# Powermeter.net
KiCad netlist of a schematic drawn in EAGLE
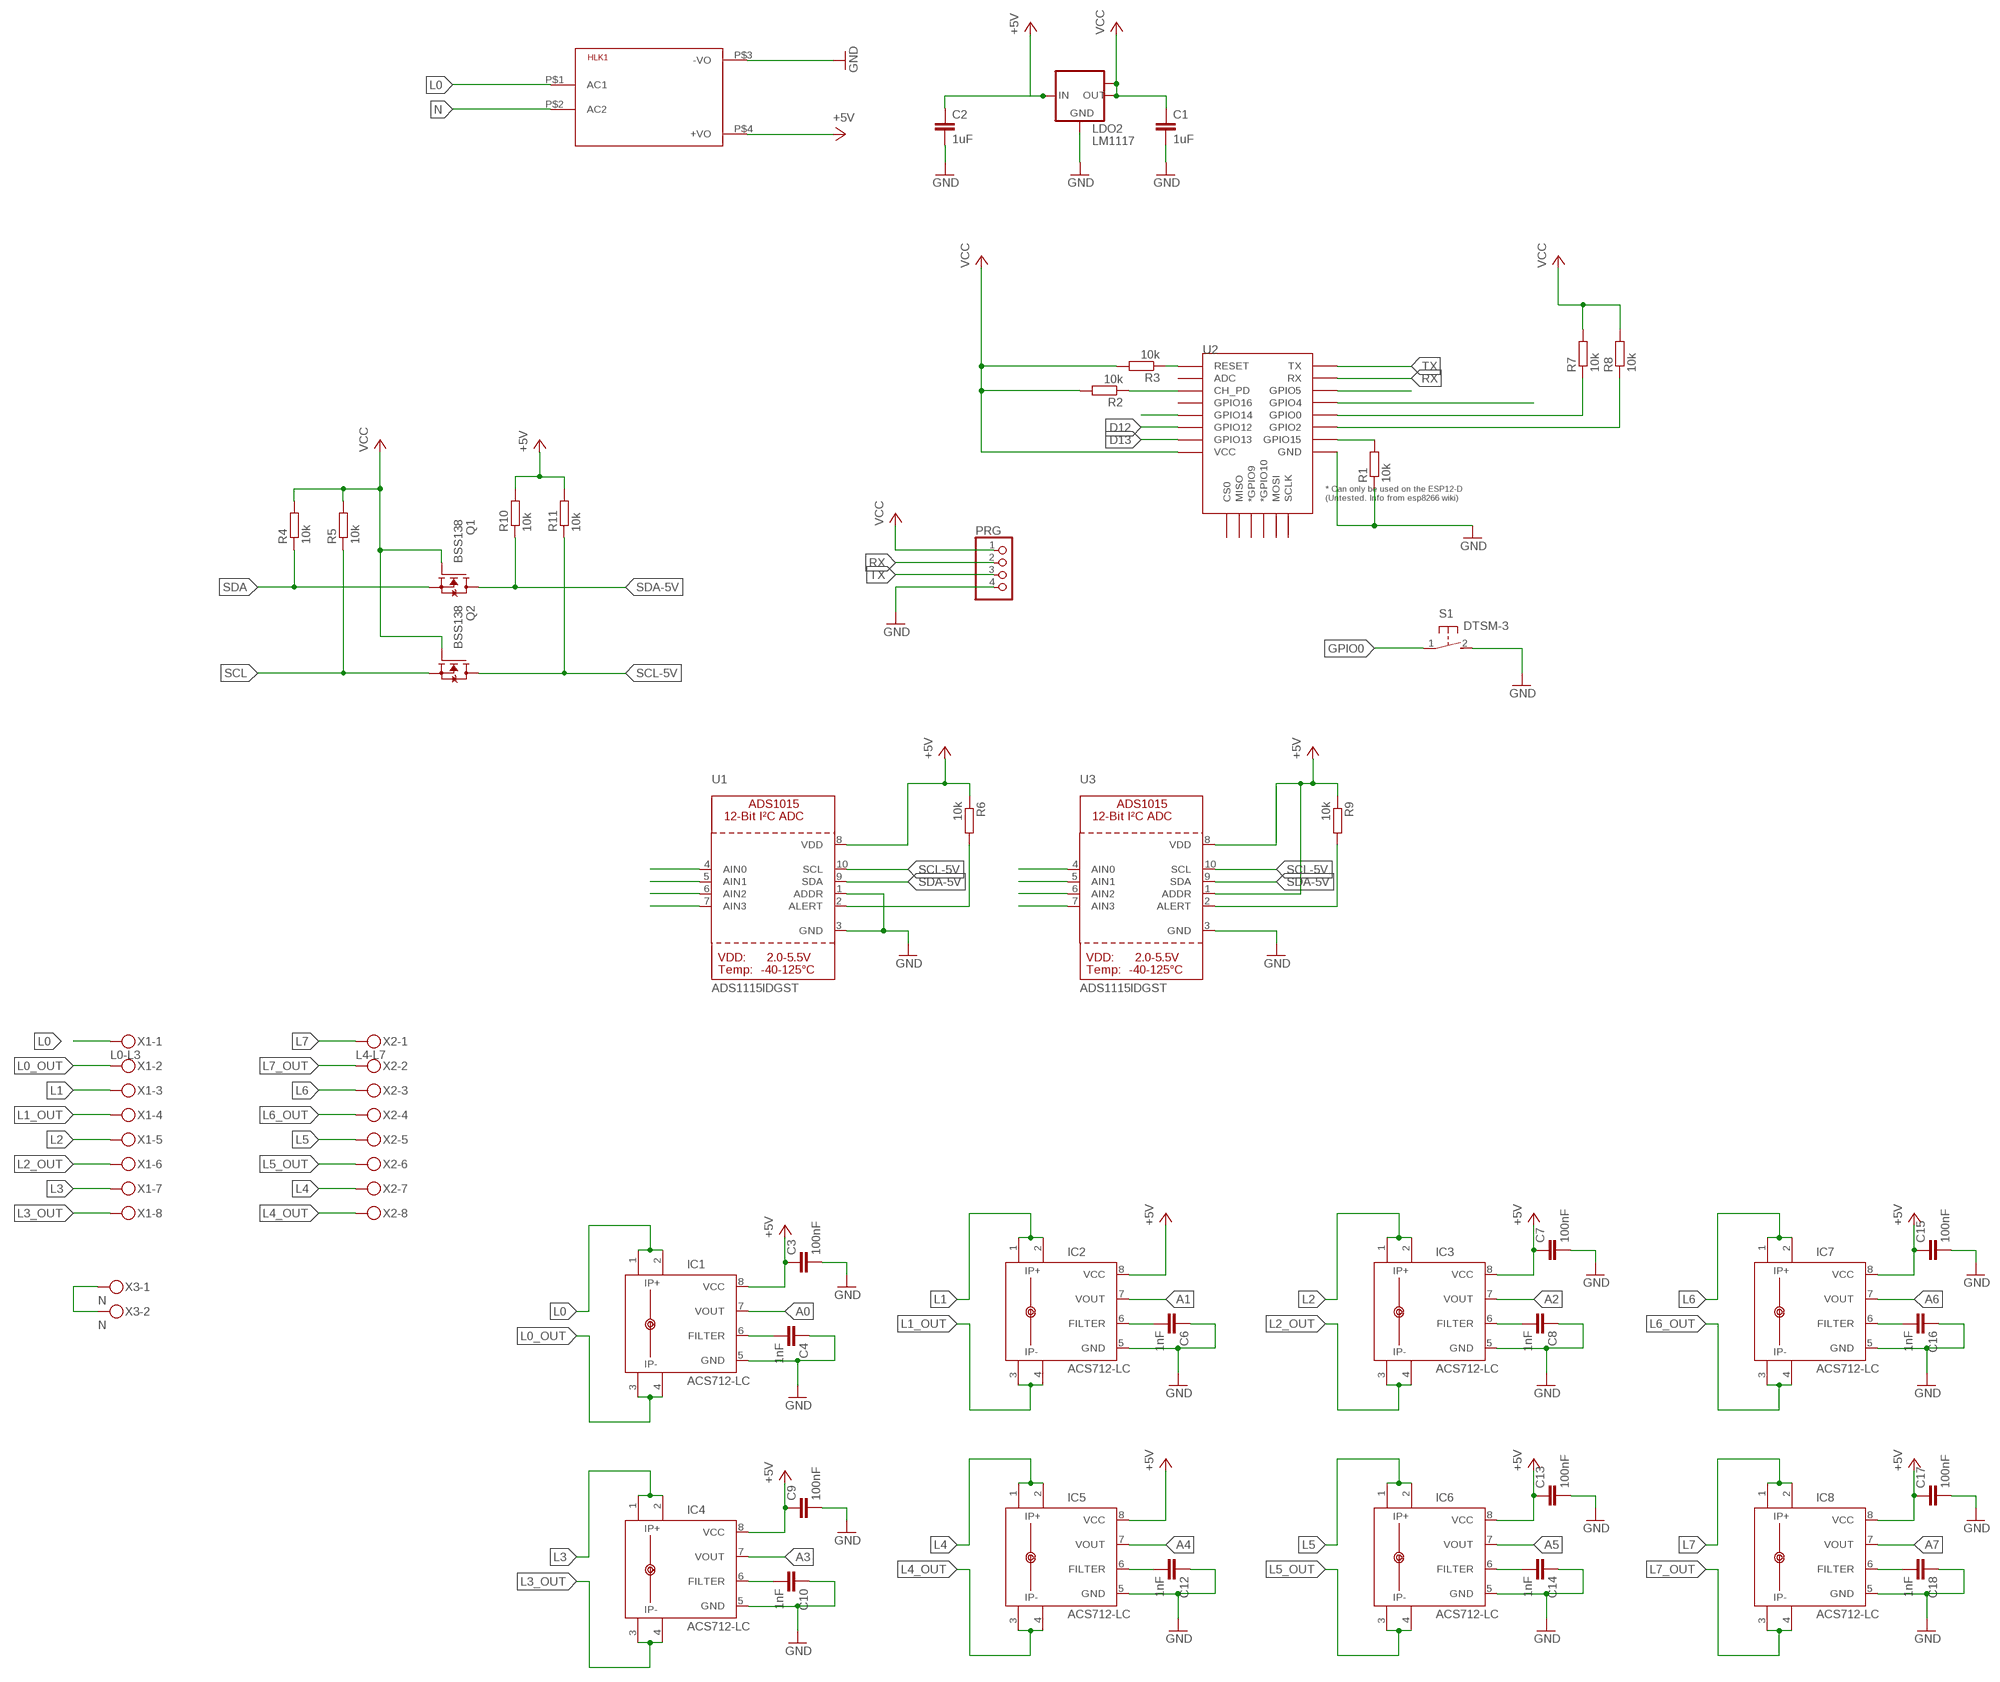
[diagram p0: schematic, sheet 1]

(export (version "E")
  (design (tool "Eeschema 10.0.6"))
  (components
    (comp (ref "C1")
      (value "1uF")
      (footprint "eagle-import:C0805")
      (libsource (lib "eagle-import") (part "C-EUC0805"))
    )
    (comp (ref "C2")
      (value "1uF")
      (footprint "eagle-import:C0805")
      (libsource (lib "eagle-import") (part "C-EUC0805"))
    )
    (comp (ref "C3")
      (value "100nF")
      (footprint "eagle-import:C0805")
      (libsource (lib "eagle-import") (part "C-EUC0805"))
    )
    (comp (ref "C4")
      (value "1nF")
      (footprint "eagle-import:C0805")
      (libsource (lib "eagle-import") (part "C-EUC0805"))
    )
    (comp (ref "C6")
      (value "1nF")
      (footprint "eagle-import:C0805")
      (libsource (lib "eagle-import") (part "C-EUC0805"))
    )
    (comp (ref "C7")
      (value "100nF")
      (footprint "eagle-import:C0805")
      (libsource (lib "eagle-import") (part "C-EUC0805"))
    )
    (comp (ref "C8")
      (value "1nF")
      (footprint "eagle-import:C0805")
      (libsource (lib "eagle-import") (part "C-EUC0805"))
    )
    (comp (ref "C9")
      (value "100nF")
      (footprint "eagle-import:C0805")
      (libsource (lib "eagle-import") (part "C-EUC0805"))
    )
    (comp (ref "C10")
      (value "1nF")
      (footprint "eagle-import:C0805")
      (libsource (lib "eagle-import") (part "C-EUC0805"))
    )
    (comp (ref "C12")
      (value "1nF")
      (footprint "eagle-import:C0805")
      (libsource (lib "eagle-import") (part "C-EUC0805"))
    )
    (comp (ref "C13")
      (value "100nF")
      (footprint "eagle-import:C0805")
      (libsource (lib "eagle-import") (part "C-EUC0805"))
    )
    (comp (ref "C14")
      (value "1nF")
      (footprint "eagle-import:C0805")
      (libsource (lib "eagle-import") (part "C-EUC0805"))
    )
    (comp (ref "C15")
      (value "100nF")
      (footprint "eagle-import:C0805")
      (libsource (lib "eagle-import") (part "C-EUC0805"))
    )
    (comp (ref "C16")
      (value "1nF")
      (footprint "eagle-import:C0805")
      (libsource (lib "eagle-import") (part "C-EUC0805"))
    )
    (comp (ref "C17")
      (value "100nF")
      (footprint "eagle-import:C0805")
      (libsource (lib "eagle-import") (part "C-EUC0805"))
    )
    (comp (ref "C18")
      (value "1nF")
      (footprint "eagle-import:C0805")
      (libsource (lib "eagle-import") (part "C-EUC0805"))
    )
    (comp (ref "HLK1")
      (value "HLK-PM013W")
      (footprint "eagle-import:HLK-PM01")
      (libsource (lib "eagle-import") (part "HLK-PM013W"))
    )
    (comp (ref "IC1")
      (value "ACS712-LC")
      (footprint "eagle-import:SOIC8")
      (libsource (lib "eagle-import") (part "ACS712-LC"))
    )
    (comp (ref "IC2")
      (value "ACS712-LC")
      (footprint "eagle-import:SOIC8")
      (libsource (lib "eagle-import") (part "ACS712-LC"))
    )
    (comp (ref "IC3")
      (value "ACS712-LC")
      (footprint "eagle-import:SOIC8")
      (libsource (lib "eagle-import") (part "ACS712-LC"))
    )
    (comp (ref "IC4")
      (value "ACS712-LC")
      (footprint "eagle-import:SOIC8")
      (libsource (lib "eagle-import") (part "ACS712-LC"))
    )
    (comp (ref "IC5")
      (value "ACS712-LC")
      (footprint "eagle-import:SOIC8")
      (libsource (lib "eagle-import") (part "ACS712-LC"))
    )
    (comp (ref "IC6")
      (value "ACS712-LC")
      (footprint "eagle-import:SOIC8")
      (libsource (lib "eagle-import") (part "ACS712-LC"))
    )
    (comp (ref "IC7")
      (value "ACS712-LC")
      (footprint "eagle-import:SOIC8")
      (libsource (lib "eagle-import") (part "ACS712-LC"))
    )
    (comp (ref "IC8")
      (value "ACS712-LC")
      (footprint "eagle-import:SOIC8")
      (libsource (lib "eagle-import") (part "ACS712-LC"))
    )
    (comp (ref "LDO2")
      (value "LM1117")
      (footprint "eagle-import:SOT223")
      (libsource (lib "eagle-import") (part "LM1117MPX-3.3"))
    )
    (comp (ref "PRG")
      (value "PINHD-1X04_2.54-S")
      (footprint "eagle-import:1X04-S")
      (libsource (lib "eagle-import") (part "PINHD-1X04_2.54-S"))
    )
    (comp (ref "Q1")
      (value "BSS138")
      (footprint "eagle-import:SOT23")
      (fields (field (name "MF") "Fairchild"))
      (libsource (lib "eagle-import") (part "BSS138"))
    )
    (comp (ref "Q2")
      (value "BSS138")
      (footprint "eagle-import:SOT23")
      (fields (field (name "MF") "Fairchild"))
      (libsource (lib "eagle-import") (part "BSS138"))
    )
    (comp (ref "R1")
      (value "10k")
      (footprint "eagle-import:R0805")
      (libsource (lib "eagle-import") (part "R-EU_R0805"))
    )
    (comp (ref "R2")
      (value "10k")
      (footprint "eagle-import:R0805")
      (libsource (lib "eagle-import") (part "R-EU_R0805"))
    )
    (comp (ref "R3")
      (value "10k")
      (footprint "eagle-import:R0805")
      (libsource (lib "eagle-import") (part "R-EU_R0805"))
    )
    (comp (ref "R4")
      (value "10k")
      (footprint "eagle-import:R0805")
      (libsource (lib "eagle-import") (part "R-EU_R0805"))
    )
    (comp (ref "R5")
      (value "10k")
      (footprint "eagle-import:R0805")
      (libsource (lib "eagle-import") (part "R-EU_R0805"))
    )
    (comp (ref "R6")
      (value "10k")
      (footprint "eagle-import:R0805")
      (libsource (lib "eagle-import") (part "R-EU_R0805"))
    )
    (comp (ref "R7")
      (value "10k")
      (footprint "eagle-import:R0805")
      (libsource (lib "eagle-import") (part "R-EU_R0805"))
    )
    (comp (ref "R8")
      (value "10k")
      (footprint "eagle-import:R0805")
      (libsource (lib "eagle-import") (part "R-EU_R0805"))
    )
    (comp (ref "R9")
      (value "10k")
      (footprint "eagle-import:R0805")
      (libsource (lib "eagle-import") (part "R-EU_R0805"))
    )
    (comp (ref "R10")
      (value "10k")
      (footprint "eagle-import:R0805")
      (libsource (lib "eagle-import") (part "R-EU_R0805"))
    )
    (comp (ref "R11")
      (value "10k")
      (footprint "eagle-import:R0805")
      (libsource (lib "eagle-import") (part "R-EU_R0805"))
    )
    (comp (ref "S1")
      (value "DTSM-3")
      (footprint "eagle-import:DTSM-3")
      (libsource (lib "eagle-import") (part "DTSM-3"))
    )
    (comp (ref "U1")
      (value "ADS1115IDGST")
      (footprint "eagle-import:MSOP10")
      (libsource (lib "eagle-import") (part "ADC_ADS1015"))
    )
    (comp (ref "U2")
      (value "ESP12ESMD")
      (footprint "eagle-import:ESP12E-SMD")
      (libsource (lib "eagle-import") (part "ESP12ESMD"))
    )
    (comp (ref "U3")
      (value "ADS1115IDGST")
      (footprint "eagle-import:MSOP10")
      (libsource (lib "eagle-import") (part "ADC_ADS1015"))
    )
    (comp (ref "X1")
      (value "L0-L3")
      (footprint "eagle-import:MKDSN1,5_8-5,08")
      (libsource (lib "eagle-import") (part "MKDSN1,5/8-5,08"))
    )
    (comp (ref "X2")
      (value "L4-L7")
      (footprint "eagle-import:MKDSN1,5_8-5,08")
      (libsource (lib "eagle-import") (part "MKDSN1,5/8-5,08"))
    )
    (comp (ref "X3")
      (value "N")
      (footprint "eagle-import:MKDSN1,5_2-5,08")
      (libsource (lib "eagle-import") (part "MKDSN1,5/2-5,08"))
    )
  )
  (nets
    (net (code "1") (name "+5V") (class "Default")
      (node (ref "C13") (pin "1") (pinfunction "1_1") (pintype "passive"))
      (node (ref "C15") (pin "1") (pinfunction "1_1") (pintype "passive"))
      (node (ref "C17") (pin "1") (pinfunction "1_1") (pintype "passive"))
      (node (ref "C2") (pin "1") (pinfunction "1_1") (pintype "passive"))
      (node (ref "C3") (pin "1") (pinfunction "1_1") (pintype "passive"))
      (node (ref "C7") (pin "1") (pinfunction "1_1") (pintype "passive"))
      (node (ref "C9") (pin "1") (pinfunction "1_1") (pintype "passive"))
      (node (ref "HLK1") (pin "P$4") (pinfunction "+VO_P$4") (pintype "bidirectional"))
      (node (ref "IC1") (pin "8") (pinfunction "VCC_8") (pintype "power_in"))
      (node (ref "IC2") (pin "8") (pinfunction "VCC_8") (pintype "power_in"))
      (node (ref "IC3") (pin "8") (pinfunction "VCC_8") (pintype "power_in"))
      (node (ref "IC4") (pin "8") (pinfunction "VCC_8") (pintype "power_in"))
      (node (ref "IC5") (pin "8") (pinfunction "VCC_8") (pintype "power_in"))
      (node (ref "IC6") (pin "8") (pinfunction "VCC_8") (pintype "power_in"))
      (node (ref "IC7") (pin "8") (pinfunction "VCC_8") (pintype "power_in"))
      (node (ref "IC8") (pin "8") (pinfunction "VCC_8") (pintype "power_in"))
      (node (ref "LDO2") (pin "3") (pinfunction "IN_3") (pintype "input"))
      (node (ref "R10") (pin "2") (pinfunction "2_2") (pintype "passive"))
      (node (ref "R11") (pin "2") (pinfunction "2_2") (pintype "passive"))
      (node (ref "R6") (pin "1") (pinfunction "1_1") (pintype "passive"))
      (node (ref "R9") (pin "1") (pinfunction "1_1") (pintype "passive"))
      (node (ref "U1") (pin "8") (pinfunction "VDD_8") (pintype "bidirectional"))
      (node (ref "U3") (pin "1") (pinfunction "ADDR_1") (pintype "bidirectional"))
      (node (ref "U3") (pin "8") (pinfunction "VDD_8") (pintype "bidirectional"))
    )
    (net (code "2") (name "A0") (class "Default")
      (node (ref "IC1") (pin "7") (pinfunction "VOUT_7") (pintype "output"))
      (node (ref "U1") (pin "4") (pinfunction "AIN0_4") (pintype "bidirectional"))
    )
    (net (code "3") (name "A1") (class "Default")
      (node (ref "IC2") (pin "7") (pinfunction "VOUT_7") (pintype "output"))
      (node (ref "U1") (pin "5") (pinfunction "AIN1_5") (pintype "bidirectional"))
    )
    (net (code "4") (name "A2") (class "Default")
      (node (ref "IC3") (pin "7") (pinfunction "VOUT_7") (pintype "output"))
      (node (ref "U1") (pin "6") (pinfunction "AIN2_6") (pintype "bidirectional"))
    )
    (net (code "5") (name "A3") (class "Default")
      (node (ref "IC4") (pin "7") (pinfunction "VOUT_7") (pintype "output"))
      (node (ref "U1") (pin "7") (pinfunction "AIN3_7") (pintype "bidirectional"))
    )
    (net (code "6") (name "A4") (class "Default")
      (node (ref "IC5") (pin "7") (pinfunction "VOUT_7") (pintype "output"))
      (node (ref "U3") (pin "4") (pinfunction "AIN0_4") (pintype "bidirectional"))
    )
    (net (code "7") (name "A5") (class "Default")
      (node (ref "IC6") (pin "7") (pinfunction "VOUT_7") (pintype "output"))
      (node (ref "U3") (pin "5") (pinfunction "AIN1_5") (pintype "bidirectional"))
    )
    (net (code "8") (name "A6") (class "Default")
      (node (ref "IC7") (pin "7") (pinfunction "VOUT_7") (pintype "output"))
      (node (ref "U3") (pin "6") (pinfunction "AIN2_6") (pintype "bidirectional"))
    )
    (net (code "9") (name "A7") (class "Default")
      (node (ref "IC8") (pin "7") (pinfunction "VOUT_7") (pintype "output"))
      (node (ref "U3") (pin "7") (pinfunction "AIN3_7") (pintype "bidirectional"))
    )
    (net (code "10") (name "D12") (class "Default")
      (node (ref "U2") (pin "GPIO12") (pinfunction "GPIO12_GPIO12") (pintype "bidirectional"))
    )
    (net (code "11") (name "D13") (class "Default")
      (node (ref "U2") (pin "GPIO13") (pinfunction "GPIO13_GPIO13") (pintype "bidirectional"))
    )
    (net (code "12") (name "GND") (class "Default")
      (node (ref "C1") (pin "2") (pinfunction "2_2") (pintype "passive"))
      (node (ref "C10") (pin "1") (pinfunction "1_1") (pintype "passive"))
      (node (ref "C12") (pin "1") (pinfunction "1_1") (pintype "passive"))
      (node (ref "C13") (pin "2") (pinfunction "2_2") (pintype "passive"))
      (node (ref "C14") (pin "1") (pinfunction "1_1") (pintype "passive"))
      (node (ref "C15") (pin "2") (pinfunction "2_2") (pintype "passive"))
      (node (ref "C16") (pin "1") (pinfunction "1_1") (pintype "passive"))
      (node (ref "C17") (pin "2") (pinfunction "2_2") (pintype "passive"))
      (node (ref "C18") (pin "1") (pinfunction "1_1") (pintype "passive"))
      (node (ref "C2") (pin "2") (pinfunction "2_2") (pintype "passive"))
      (node (ref "C3") (pin "2") (pinfunction "2_2") (pintype "passive"))
      (node (ref "C4") (pin "1") (pinfunction "1_1") (pintype "passive"))
      (node (ref "C6") (pin "1") (pinfunction "1_1") (pintype "passive"))
      (node (ref "C7") (pin "2") (pinfunction "2_2") (pintype "passive"))
      (node (ref "C8") (pin "1") (pinfunction "1_1") (pintype "passive"))
      (node (ref "C9") (pin "2") (pinfunction "2_2") (pintype "passive"))
      (node (ref "HLK1") (pin "P$3") (pinfunction "-VO_P$3") (pintype "bidirectional"))
      (node (ref "IC1") (pin "5") (pinfunction "GND_5") (pintype "power_in"))
      (node (ref "IC2") (pin "5") (pinfunction "GND_5") (pintype "power_in"))
      (node (ref "IC3") (pin "5") (pinfunction "GND_5") (pintype "power_in"))
      (node (ref "IC4") (pin "5") (pinfunction "GND_5") (pintype "power_in"))
      (node (ref "IC5") (pin "5") (pinfunction "GND_5") (pintype "power_in"))
      (node (ref "IC6") (pin "5") (pinfunction "GND_5") (pintype "power_in"))
      (node (ref "IC7") (pin "5") (pinfunction "GND_5") (pintype "power_in"))
      (node (ref "IC8") (pin "5") (pinfunction "GND_5") (pintype "power_in"))
      (node (ref "LDO2") (pin "1") (pinfunction "GND_1") (pintype "input"))
      (node (ref "PRG") (pin "4") (pinfunction "4_4") (pintype "passive"))
      (node (ref "R1") (pin "1") (pinfunction "1_1") (pintype "passive"))
      (node (ref "S1") (pin "2") (pinfunction "2_2") (pintype "passive"))
      (node (ref "U1") (pin "1") (pinfunction "ADDR_1") (pintype "bidirectional"))
      (node (ref "U1") (pin "3") (pinfunction "GND_3") (pintype "bidirectional"))
      (node (ref "U2") (pin "GND") (pinfunction "GND_GND") (pintype "bidirectional"))
      (node (ref "U3") (pin "3") (pinfunction "GND_3") (pintype "bidirectional"))
    )
    (net (code "13") (name "GPIO0") (class "Default")
      (node (ref "R7") (pin "1") (pinfunction "1_1") (pintype "passive"))
      (node (ref "S1") (pin "1") (pinfunction "1_1") (pintype "passive"))
      (node (ref "U2") (pin "GPIO0") (pinfunction "GPIO0_GPIO0") (pintype "bidirectional"))
    )
    (net (code "14") (name "L0") (class "Default")
      (node (ref "HLK1") (pin "P$1") (pinfunction "AC1_P$1") (pintype "bidirectional"))
      (node (ref "IC1") (pin "1") (pinfunction "IP+_1") (pintype "passive"))
      (node (ref "IC1") (pin "2") (pinfunction "IP+1_2") (pintype "passive"))
      (node (ref "X1") (pin "1") (pinfunction "KL_1") (pintype "passive"))
    )
    (net (code "15") (name "L0_OUT") (class "Default")
      (node (ref "IC1") (pin "3") (pinfunction "IP-_3") (pintype "passive"))
      (node (ref "IC1") (pin "4") (pinfunction "IP-1_4") (pintype "passive"))
      (node (ref "X1") (pin "2") (pinfunction "KL_2") (pintype "passive"))
    )
    (net (code "16") (name "L1") (class "Default")
      (node (ref "IC2") (pin "1") (pinfunction "IP+_1") (pintype "passive"))
      (node (ref "IC2") (pin "2") (pinfunction "IP+1_2") (pintype "passive"))
      (node (ref "X1") (pin "3") (pinfunction "KL_3") (pintype "passive"))
    )
    (net (code "17") (name "L1_OUT") (class "Default")
      (node (ref "IC2") (pin "3") (pinfunction "IP-_3") (pintype "passive"))
      (node (ref "IC2") (pin "4") (pinfunction "IP-1_4") (pintype "passive"))
      (node (ref "X1") (pin "4") (pinfunction "KL_4") (pintype "passive"))
    )
    (net (code "18") (name "L2") (class "Default")
      (node (ref "IC3") (pin "1") (pinfunction "IP+_1") (pintype "passive"))
      (node (ref "IC3") (pin "2") (pinfunction "IP+1_2") (pintype "passive"))
      (node (ref "X1") (pin "5") (pinfunction "KL_5") (pintype "passive"))
    )
    (net (code "19") (name "L2_OUT") (class "Default")
      (node (ref "IC3") (pin "3") (pinfunction "IP-_3") (pintype "passive"))
      (node (ref "IC3") (pin "4") (pinfunction "IP-1_4") (pintype "passive"))
      (node (ref "X1") (pin "6") (pinfunction "KL_6") (pintype "passive"))
    )
    (net (code "20") (name "L3") (class "Default")
      (node (ref "IC4") (pin "1") (pinfunction "IP+_1") (pintype "passive"))
      (node (ref "IC4") (pin "2") (pinfunction "IP+1_2") (pintype "passive"))
      (node (ref "X1") (pin "7") (pinfunction "KL_7") (pintype "passive"))
    )
    (net (code "21") (name "L3_OUT") (class "Default")
      (node (ref "IC4") (pin "3") (pinfunction "IP-_3") (pintype "passive"))
      (node (ref "IC4") (pin "4") (pinfunction "IP-1_4") (pintype "passive"))
      (node (ref "X1") (pin "8") (pinfunction "KL_8") (pintype "passive"))
    )
    (net (code "22") (name "L4") (class "Default")
      (node (ref "IC5") (pin "1") (pinfunction "IP+_1") (pintype "passive"))
      (node (ref "IC5") (pin "2") (pinfunction "IP+1_2") (pintype "passive"))
      (node (ref "X2") (pin "7") (pinfunction "KL_7") (pintype "passive"))
    )
    (net (code "23") (name "L4_OUT") (class "Default")
      (node (ref "IC5") (pin "3") (pinfunction "IP-_3") (pintype "passive"))
      (node (ref "IC5") (pin "4") (pinfunction "IP-1_4") (pintype "passive"))
      (node (ref "X2") (pin "8") (pinfunction "KL_8") (pintype "passive"))
    )
    (net (code "24") (name "L5") (class "Default")
      (node (ref "IC6") (pin "1") (pinfunction "IP+_1") (pintype "passive"))
      (node (ref "IC6") (pin "2") (pinfunction "IP+1_2") (pintype "passive"))
      (node (ref "X2") (pin "5") (pinfunction "KL_5") (pintype "passive"))
    )
    (net (code "25") (name "L5_OUT") (class "Default")
      (node (ref "IC6") (pin "3") (pinfunction "IP-_3") (pintype "passive"))
      (node (ref "IC6") (pin "4") (pinfunction "IP-1_4") (pintype "passive"))
      (node (ref "X2") (pin "6") (pinfunction "KL_6") (pintype "passive"))
    )
    (net (code "26") (name "L6") (class "Default")
      (node (ref "IC7") (pin "1") (pinfunction "IP+_1") (pintype "passive"))
      (node (ref "IC7") (pin "2") (pinfunction "IP+1_2") (pintype "passive"))
      (node (ref "X2") (pin "3") (pinfunction "KL_3") (pintype "passive"))
    )
    (net (code "27") (name "L6_OUT") (class "Default")
      (node (ref "IC7") (pin "3") (pinfunction "IP-_3") (pintype "passive"))
      (node (ref "IC7") (pin "4") (pinfunction "IP-1_4") (pintype "passive"))
      (node (ref "X2") (pin "4") (pinfunction "KL_4") (pintype "passive"))
    )
    (net (code "28") (name "L7") (class "Default")
      (node (ref "IC8") (pin "1") (pinfunction "IP+_1") (pintype "passive"))
      (node (ref "IC8") (pin "2") (pinfunction "IP+1_2") (pintype "passive"))
      (node (ref "X2") (pin "1") (pinfunction "KL_1") (pintype "passive"))
    )
    (net (code "29") (name "L7_OUT") (class "Default")
      (node (ref "IC8") (pin "3") (pinfunction "IP-_3") (pintype "passive"))
      (node (ref "IC8") (pin "4") (pinfunction "IP-1_4") (pintype "passive"))
      (node (ref "X2") (pin "2") (pinfunction "KL_2") (pintype "passive"))
    )
    (net (code "30") (name "N") (class "Default")
      (node (ref "HLK1") (pin "P$2") (pinfunction "AC2_P$2") (pintype "bidirectional"))
      (node (ref "X3") (pin "1") (pinfunction "KL_1") (pintype "passive"))
      (node (ref "X3") (pin "2") (pinfunction "KL_2") (pintype "passive"))
    )
    (net (code "31") (name "Net-(IC1-FILTER)") (class "Default")
      (node (ref "C4") (pin "2") (pinfunction "2_2") (pintype "passive"))
      (node (ref "IC1") (pin "6") (pinfunction "FILTER_6") (pintype "bidirectional"))
    )
    (net (code "32") (name "Net-(IC2-FILTER)") (class "Default")
      (node (ref "C6") (pin "2") (pinfunction "2_2") (pintype "passive"))
      (node (ref "IC2") (pin "6") (pinfunction "FILTER_6") (pintype "bidirectional"))
    )
    (net (code "33") (name "Net-(IC3-FILTER)") (class "Default")
      (node (ref "C8") (pin "2") (pinfunction "2_2") (pintype "passive"))
      (node (ref "IC3") (pin "6") (pinfunction "FILTER_6") (pintype "bidirectional"))
    )
    (net (code "34") (name "Net-(IC4-FILTER)") (class "Default")
      (node (ref "C10") (pin "2") (pinfunction "2_2") (pintype "passive"))
      (node (ref "IC4") (pin "6") (pinfunction "FILTER_6") (pintype "bidirectional"))
    )
    (net (code "35") (name "Net-(IC5-FILTER)") (class "Default")
      (node (ref "C12") (pin "2") (pinfunction "2_2") (pintype "passive"))
      (node (ref "IC5") (pin "6") (pinfunction "FILTER_6") (pintype "bidirectional"))
    )
    (net (code "36") (name "Net-(IC6-FILTER)") (class "Default")
      (node (ref "C14") (pin "2") (pinfunction "2_2") (pintype "passive"))
      (node (ref "IC6") (pin "6") (pinfunction "FILTER_6") (pintype "bidirectional"))
    )
    (net (code "37") (name "Net-(IC7-FILTER)") (class "Default")
      (node (ref "C16") (pin "2") (pinfunction "2_2") (pintype "passive"))
      (node (ref "IC7") (pin "6") (pinfunction "FILTER_6") (pintype "bidirectional"))
    )
    (net (code "38") (name "Net-(IC8-FILTER)") (class "Default")
      (node (ref "C18") (pin "2") (pinfunction "2_2") (pintype "passive"))
      (node (ref "IC8") (pin "6") (pinfunction "FILTER_6") (pintype "bidirectional"))
    )
    (net (code "39") (name "Net-(R1-Pad2)") (class "Default")
      (node (ref "R1") (pin "2") (pinfunction "2_2") (pintype "passive"))
      (node (ref "U2") (pin "GPIO15") (pinfunction "GPIO15_GPIO15") (pintype "bidirectional"))
    )
    (net (code "40") (name "Net-(R2-Pad1)") (class "Default")
      (node (ref "R2") (pin "1") (pinfunction "1_1") (pintype "passive"))
      (node (ref "U2") (pin "CH_PD") (pinfunction "CH_PD_CH_PD") (pintype "bidirectional"))
    )
    (net (code "41") (name "Net-(R3-Pad1)") (class "Default")
      (node (ref "R3") (pin "1") (pinfunction "1_1") (pintype "passive"))
      (node (ref "U2") (pin "RESET") (pinfunction "RESET_RESET") (pintype "bidirectional"))
    )
    (net (code "42") (name "Net-(R8-Pad1)") (class "Default")
      (node (ref "R8") (pin "1") (pinfunction "1_1") (pintype "passive"))
      (node (ref "U2") (pin "GPIO2") (pinfunction "GPIO2_GPIO2") (pintype "bidirectional"))
    )
    (net (code "43") (name "Net-(U1-ALERT)") (class "Default")
      (node (ref "R6") (pin "2") (pinfunction "2_2") (pintype "passive"))
      (node (ref "U1") (pin "2") (pinfunction "ALERT_2") (pintype "bidirectional"))
    )
    (net (code "44") (name "Net-(U3-ALERT)") (class "Default")
      (node (ref "R9") (pin "2") (pinfunction "2_2") (pintype "passive"))
      (node (ref "U3") (pin "2") (pinfunction "ALERT_2") (pintype "bidirectional"))
    )
    (net (code "45") (name "RX") (class "Default")
      (node (ref "PRG") (pin "2") (pinfunction "2_2") (pintype "passive"))
      (node (ref "U2") (pin "RXD0") (pinfunction "RX_RXD0") (pintype "bidirectional"))
    )
    (net (code "46") (name "SCL") (class "Default")
      (node (ref "Q2") (pin "2") (pinfunction "S_2") (pintype "passive"))
      (node (ref "R5") (pin "1") (pinfunction "1_1") (pintype "passive"))
      (node (ref "U2") (pin "GPIO5") (pinfunction "GPIO5_GPIO5") (pintype "bidirectional"))
    )
    (net (code "47") (name "SCL-5V") (class "Default")
      (node (ref "Q2") (pin "3") (pinfunction "D_3") (pintype "passive"))
      (node (ref "R11") (pin "1") (pinfunction "1_1") (pintype "passive"))
      (node (ref "U1") (pin "10") (pinfunction "SCL_10") (pintype "bidirectional"))
      (node (ref "U3") (pin "10") (pinfunction "SCL_10") (pintype "bidirectional"))
    )
    (net (code "48") (name "SDA") (class "Default")
      (node (ref "Q1") (pin "2") (pinfunction "S_2") (pintype "passive"))
      (node (ref "R4") (pin "1") (pinfunction "1_1") (pintype "passive"))
      (node (ref "U2") (pin "GPIO4") (pinfunction "GPIO4_GPIO4") (pintype "bidirectional"))
    )
    (net (code "49") (name "SDA-5V") (class "Default")
      (node (ref "Q1") (pin "3") (pinfunction "D_3") (pintype "passive"))
      (node (ref "R10") (pin "1") (pinfunction "1_1") (pintype "passive"))
      (node (ref "U1") (pin "9") (pinfunction "SDA_9") (pintype "bidirectional"))
      (node (ref "U3") (pin "9") (pinfunction "SDA_9") (pintype "bidirectional"))
    )
    (net (code "50") (name "TX") (class "Default")
      (node (ref "PRG") (pin "3") (pinfunction "3_3") (pintype "passive"))
      (node (ref "U2") (pin "TXD0") (pinfunction "TX_TXD0") (pintype "bidirectional"))
    )
    (net (code "51") (name "VCC") (class "Default")
      (node (ref "C1") (pin "1") (pinfunction "1_1") (pintype "passive"))
      (node (ref "LDO2") (pin "2") (pinfunction "OUT_2") (pintype "passive"))
      (node (ref "LDO2") (pin "TAB") (pinfunction "OUT1_TAB") (pintype "passive"))
      (node (ref "PRG") (pin "1") (pinfunction "1_1") (pintype "passive"))
      (node (ref "Q1") (pin "1") (pinfunction "G_1") (pintype "passive"))
      (node (ref "Q2") (pin "1") (pinfunction "G_1") (pintype "passive"))
      (node (ref "R2") (pin "2") (pinfunction "2_2") (pintype "passive"))
      (node (ref "R3") (pin "2") (pinfunction "2_2") (pintype "passive"))
      (node (ref "R4") (pin "2") (pinfunction "2_2") (pintype "passive"))
      (node (ref "R5") (pin "2") (pinfunction "2_2") (pintype "passive"))
      (node (ref "R7") (pin "2") (pinfunction "2_2") (pintype "passive"))
      (node (ref "R8") (pin "2") (pinfunction "2_2") (pintype "passive"))
      (node (ref "U2") (pin "VCC") (pinfunction "VCC_VCC") (pintype "bidirectional"))
    )
    (net (code "52") (name "unconnected-(U2-*GPIO9-PadGPIO9)") (class "Default")
      (node (ref "U2") (pin "GPIO9") (pinfunction "*GPIO9_GPIO9") (pintype "bidirectional"))
    )
    (net (code "53") (name "unconnected-(U2-*GPIO10-PadGPIO10)") (class "Default")
      (node (ref "U2") (pin "GPIO10") (pinfunction "*GPIO10_GPIO10") (pintype "bidirectional"))
    )
    (net (code "54") (name "unconnected-(U2-PadADC)") (class "Default")
      (node (ref "U2") (pin "ADC") (pinfunction "ADC_ADC") (pintype "bidirectional"))
    )
    (net (code "55") (name "unconnected-(U2-PadCS0)") (class "Default")
      (node (ref "U2") (pin "CS0") (pinfunction "CS0_CS0") (pintype "bidirectional"))
    )
    (net (code "56") (name "unconnected-(U2-PadGPIO14)") (class "Default")
      (node (ref "U2") (pin "GPIO14") (pinfunction "GPIO14_GPIO14") (pintype "bidirectional"))
    )
    (net (code "57") (name "unconnected-(U2-PadGPIO16)") (class "Default")
      (node (ref "U2") (pin "GPIO16") (pinfunction "GPIO16_GPIO16") (pintype "bidirectional"))
    )
    (net (code "58") (name "unconnected-(U2-PadMISO)") (class "Default")
      (node (ref "U2") (pin "MISO") (pinfunction "MISO_MISO") (pintype "bidirectional"))
    )
    (net (code "59") (name "unconnected-(U2-PadMOSI)") (class "Default")
      (node (ref "U2") (pin "MOSI") (pinfunction "MOSI_MOSI") (pintype "bidirectional"))
    )
    (net (code "60") (name "unconnected-(U2-PadSCLK)") (class "Default")
      (node (ref "U2") (pin "SCLK") (pinfunction "SCLK_SCLK") (pintype "bidirectional"))
    )
  )
)
